# clock_prototype.net
KiCad netlist of a schematic drawn in EAGLE
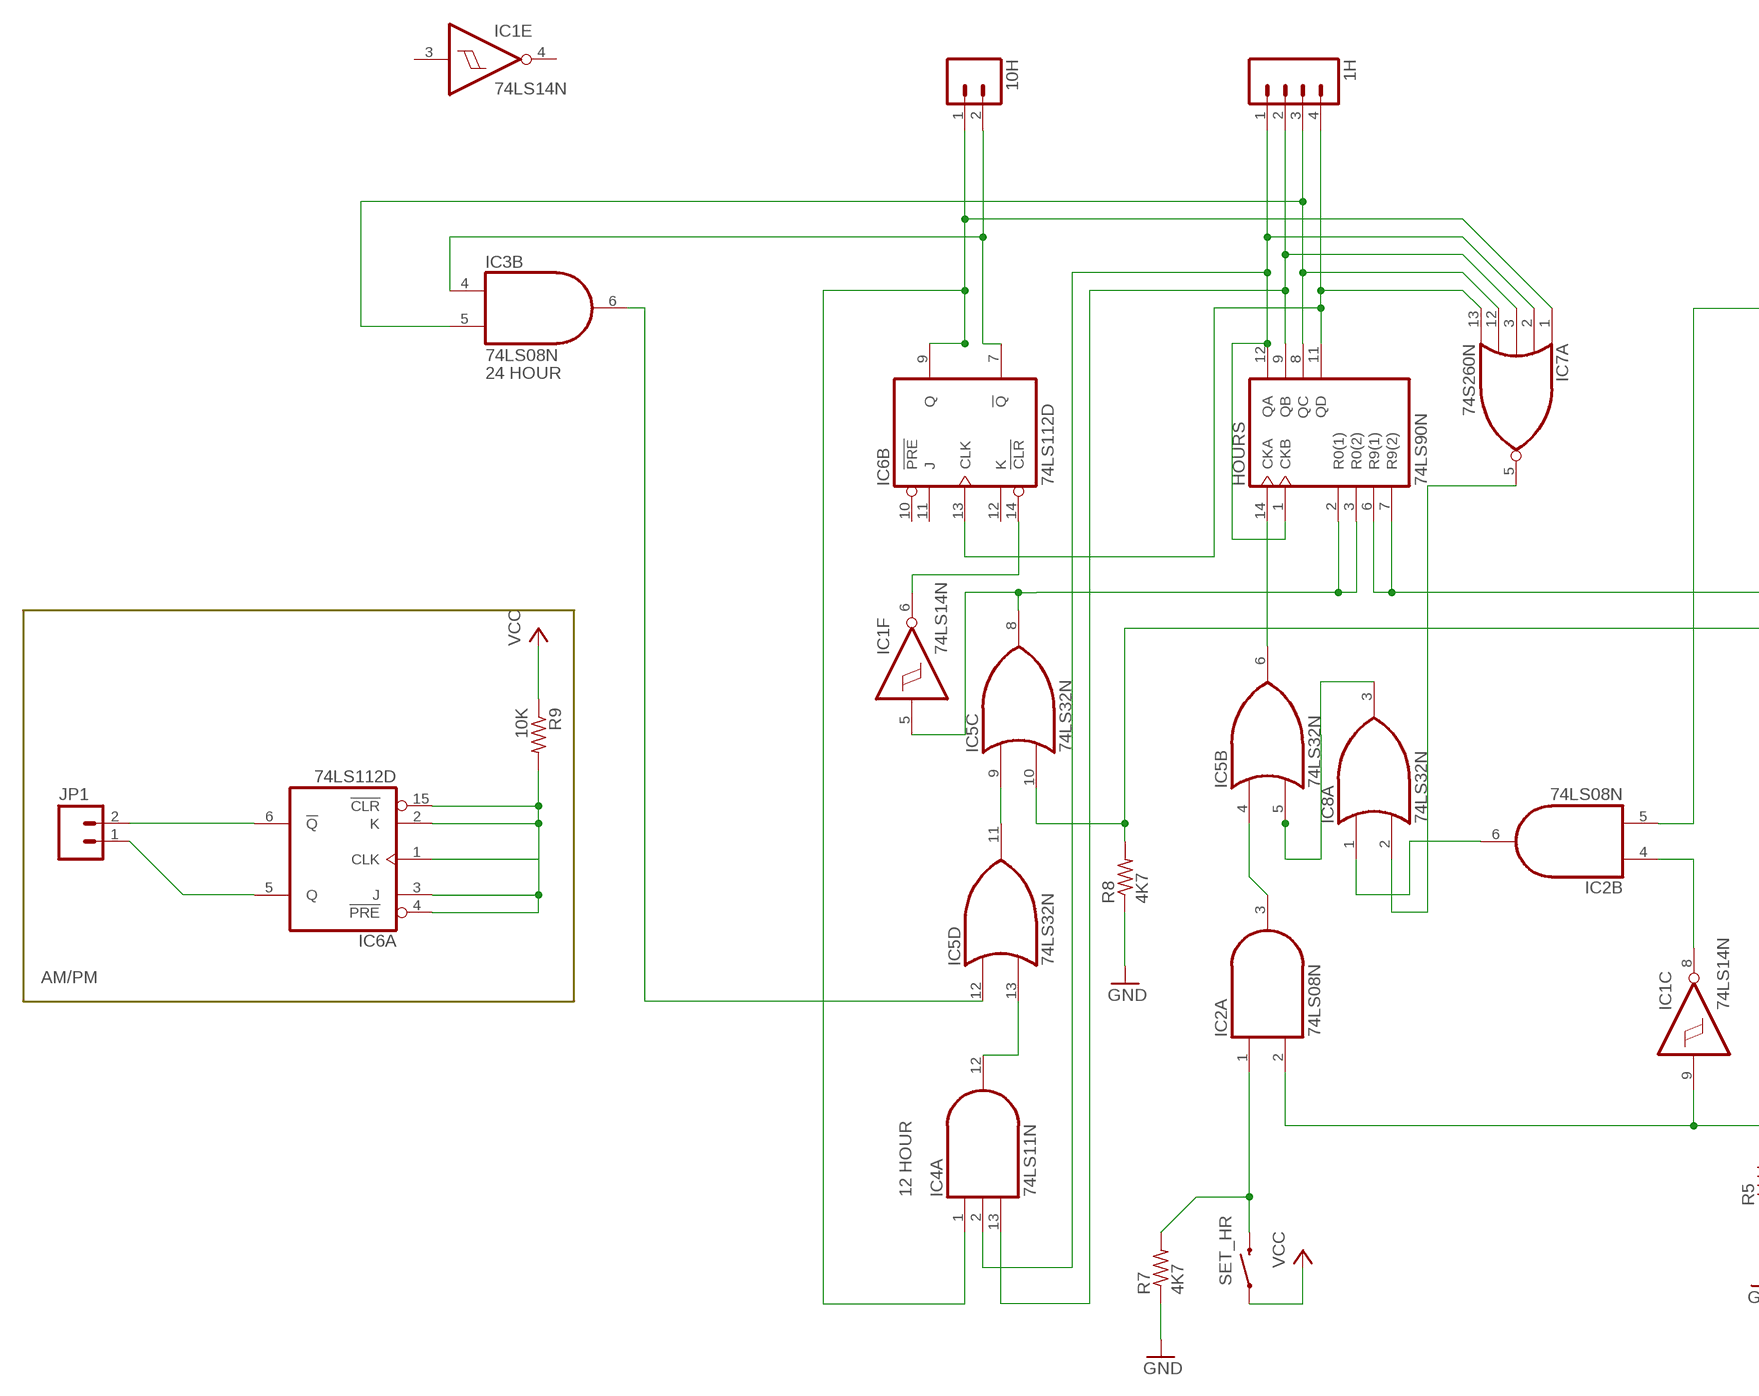
[diagram p0: schematic, sheet 1, part 1 of 2]
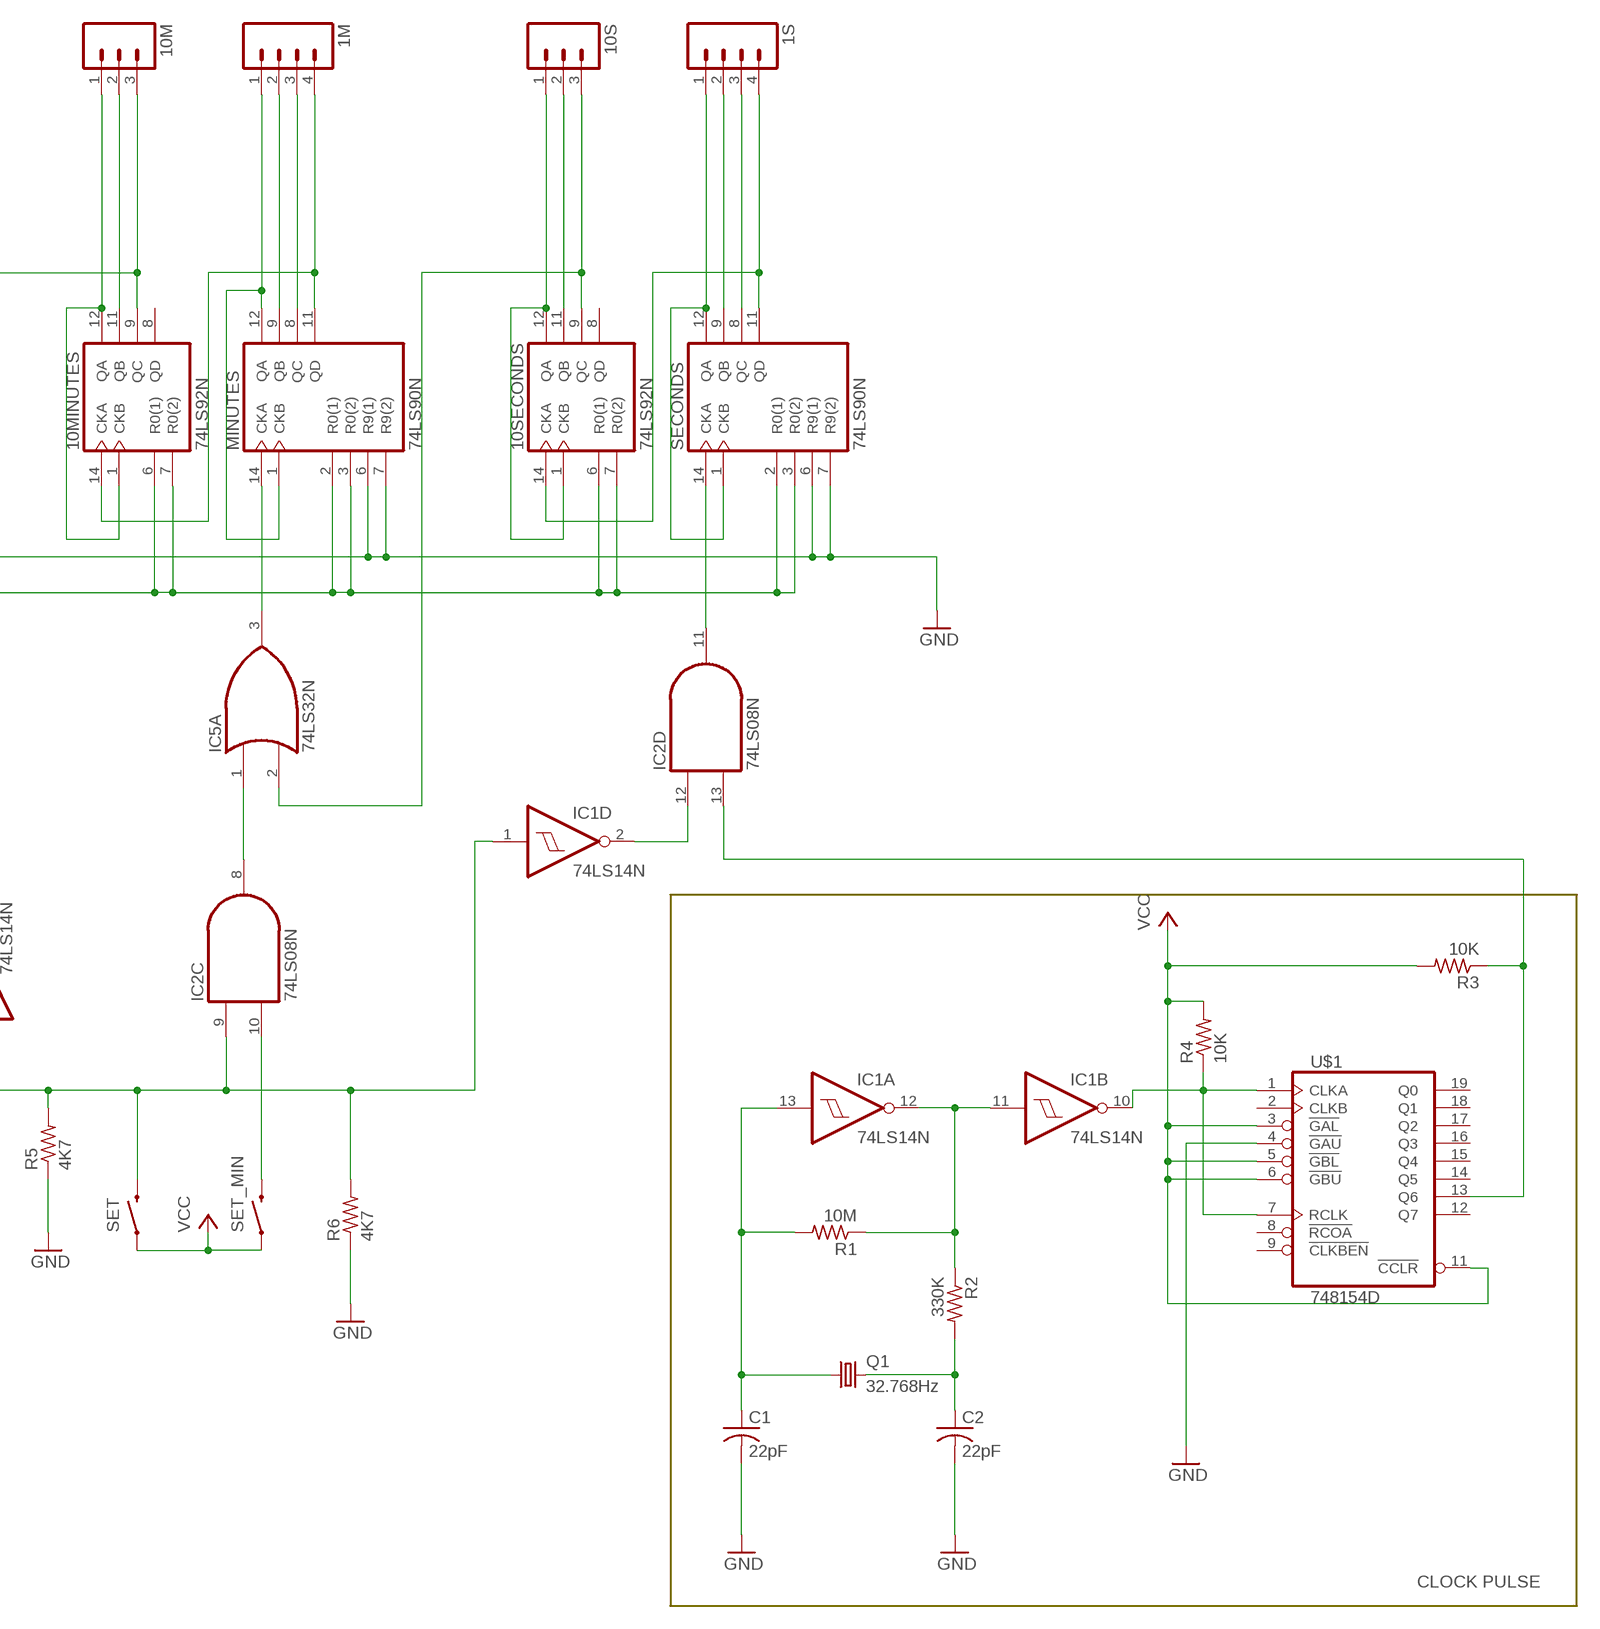
[diagram p1: schematic, sheet 1, part 2 of 2]

(export (version "E")
  (design (tool "Eeschema 10.0.6"))
  (components
    (comp (ref "1H")
      (value "M04PTH")
      (footprint "eagle-import:1X04")
      (libsource (lib "eagle-import") (part "M04PTH"))
    )
    (comp (ref "1M")
      (value "M04PTH")
      (footprint "eagle-import:1X04")
      (libsource (lib "eagle-import") (part "M04PTH"))
    )
    (comp (ref "1S")
      (value "M04PTH")
      (footprint "eagle-import:1X04")
      (libsource (lib "eagle-import") (part "M04PTH"))
    )
    (comp (ref "10H")
      (value "M02PTH")
      (footprint "eagle-import:1X02")
      (libsource (lib "eagle-import") (part "M02PTH"))
    )
    (comp (ref "10M")
      (value "M03PTH")
      (footprint "eagle-import:1X03")
      (libsource (lib "eagle-import") (part "M03PTH"))
    )
    (comp (ref "10MINUTES")
      (value "74LS92N")
      (footprint "eagle-import:DIL14")
      (libsource (lib "eagle-import") (part "7492NLS"))
    )
    (comp (ref "10S")
      (value "M03PTH")
      (footprint "eagle-import:1X03")
      (libsource (lib "eagle-import") (part "M03PTH"))
    )
    (comp (ref "10SECONDS")
      (value "74LS92N")
      (footprint "eagle-import:DIL14")
      (libsource (lib "eagle-import") (part "7492NLS"))
    )
    (comp (ref "C1")
      (value "22pF")
      (footprint "eagle-import:C050-024X044")
      (libsource (lib "eagle-import") (part "CAPACITOR050-024X044"))
    )
    (comp (ref "C2")
      (value "22pF")
      (footprint "eagle-import:C050-024X044")
      (libsource (lib "eagle-import") (part "CAPACITOR050-024X044"))
    )
    (comp (ref "HOURS")
      (value "74LS90N")
      (footprint "eagle-import:DIL14")
      (libsource (lib "eagle-import") (part "7490NLS"))
    )
    (comp (ref "IC1")
      (value "74LS14N")
      (footprint "eagle-import:DIL14")
      (libsource (lib "eagle-import") (part "7414NLS"))
    )
    (comp (ref "IC2")
      (value "74LS08N")
      (footprint "eagle-import:DIL14")
      (libsource (lib "eagle-import") (part "7408NLS"))
    )
    (comp (ref "IC3")
      (value "74LS08N")
      (footprint "eagle-import:DIL14")
      (libsource (lib "eagle-import") (part "7408NLS"))
    )
    (comp (ref "IC4")
      (value "74LS11N")
      (footprint "eagle-import:DIL14")
      (libsource (lib "eagle-import") (part "7411NLS"))
    )
    (comp (ref "IC5")
      (value "74LS32N")
      (footprint "eagle-import:DIL14")
      (libsource (lib "eagle-import") (part "7432NLS"))
    )
    (comp (ref "IC6")
      (value "74LS112D")
      (footprint "eagle-import:SO16")
      (libsource (lib "eagle-import") (part "74112DLS"))
    )
    (comp (ref "IC7")
      (value "74S260N")
      (footprint "eagle-import:DIL14")
      (libsource (lib "eagle-import") (part "74260NS"))
    )
    (comp (ref "IC8")
      (value "74LS32N")
      (footprint "eagle-import:DIL14")
      (libsource (lib "eagle-import") (part "7432NLS"))
    )
    (comp (ref "JP1")
      (value "M02PTH")
      (footprint "eagle-import:1X02")
      (libsource (lib "eagle-import") (part "M02PTH"))
    )
    (comp (ref "MINUTES")
      (value "74LS90N")
      (footprint "eagle-import:DIL14")
      (libsource (lib "eagle-import") (part "7490NLS"))
    )
    (comp (ref "Q1")
      (value "32.768Hz")
      (footprint "eagle-import:TC26V")
      (libsource (lib "eagle-import") (part "CRYSTALTC26V"))
    )
    (comp (ref "R1")
      (value "10M")
      (footprint "eagle-import:0207_7")
      (libsource (lib "eagle-import") (part "RESISTOR0207/7"))
    )
    (comp (ref "R2")
      (value "330K")
      (footprint "eagle-import:0207_7")
      (libsource (lib "eagle-import") (part "RESISTOR0207/7"))
    )
    (comp (ref "R3")
      (value "10K")
      (footprint "eagle-import:0207_7")
      (libsource (lib "eagle-import") (part "RESISTOR0207/7"))
    )
    (comp (ref "R4")
      (value "10K")
      (footprint "eagle-import:0207_7")
      (libsource (lib "eagle-import") (part "RESISTOR0207/7"))
    )
    (comp (ref "R5")
      (value "4K7")
      (footprint "eagle-import:0207_7")
      (libsource (lib "eagle-import") (part "RESISTOR0207/7"))
    )
    (comp (ref "R6")
      (value "4K7")
      (footprint "eagle-import:0207_7")
      (libsource (lib "eagle-import") (part "RESISTOR0207/7"))
    )
    (comp (ref "R7")
      (value "4K7")
      (footprint "eagle-import:0207_7")
      (libsource (lib "eagle-import") (part "RESISTOR0207/7"))
    )
    (comp (ref "R8")
      (value "4K7")
      (footprint "eagle-import:0207_7")
      (libsource (lib "eagle-import") (part "RESISTOR0207/7"))
    )
    (comp (ref "R9")
      (value "10K")
      (footprint "eagle-import:0207_7")
      (libsource (lib "eagle-import") (part "RESISTOR0207/7"))
    )
    (comp (ref "SECONDS")
      (value "74LS90N")
      (footprint "eagle-import:DIL14")
      (libsource (lib "eagle-import") (part "7490NLS"))
    )
    (comp (ref "SET")
      (value "SWITCH-MOMENTARY12MM")
      (footprint "eagle-import:TACTILE-PTH-12MM")
      (libsource (lib "eagle-import") (part "SWITCH-MOMENTARY12MM"))
    )
    (comp (ref "SET_HR")
      (value "SWITCH-MOMENTARY12MM")
      (footprint "eagle-import:TACTILE-PTH-12MM")
      (libsource (lib "eagle-import") (part "SWITCH-MOMENTARY12MM"))
    )
    (comp (ref "SET_MIN")
      (value "SWITCH-MOMENTARY12MM")
      (footprint "eagle-import:TACTILE-PTH-12MM")
      (libsource (lib "eagle-import") (part "SWITCH-MOMENTARY12MM"))
    )
    (comp (ref "U$1")
      (value "748154D")
      (footprint "eagle-import:TSSOP20")
      (libsource (lib "eagle-import") (part "748154D"))
    )
  )
  (nets
    (net (code "1") (name "GND") (class "Default")
      (node (ref "C1") (pin "2") (pinfunction "2_2") (pintype "passive"))
      (node (ref "C2") (pin "2") (pinfunction "2_2") (pintype "passive"))
      (node (ref "HOURS") (pin "6") (pinfunction "R9(1)_6") (pintype "input"))
      (node (ref "HOURS") (pin "7") (pinfunction "R9(2)_7") (pintype "input"))
      (node (ref "MINUTES") (pin "6") (pinfunction "R9(1)_6") (pintype "input"))
      (node (ref "MINUTES") (pin "7") (pinfunction "R9(2)_7") (pintype "input"))
      (node (ref "R5") (pin "1") (pinfunction "1_1") (pintype "passive"))
      (node (ref "R6") (pin "1") (pinfunction "1_1") (pintype "passive"))
      (node (ref "R7") (pin "1") (pinfunction "1_1") (pintype "passive"))
      (node (ref "R8") (pin "1") (pinfunction "1_1") (pintype "passive"))
      (node (ref "SECONDS") (pin "6") (pinfunction "R9(1)_6") (pintype "input"))
      (node (ref "SECONDS") (pin "7") (pinfunction "R9(2)_7") (pintype "input"))
      (node (ref "U$1") (pin "4") (pinfunction "~{GAU}_4") (pintype "input"))
    )
    (net (code "2") (name "Net-(10MINUTESA-CKA)") (class "Default")
      (node (ref "10MINUTES") (pin "14") (pinfunction "CKA_14") (pintype "input"))
      (node (ref "1M") (pin "4") (pinfunction "4_4") (pintype "passive"))
      (node (ref "MINUTES") (pin "11") (pinfunction "QD_11") (pintype "output"))
    )
    (net (code "3") (name "Net-(10MINUTESA-CKB)") (class "Default")
      (node (ref "10M") (pin "1") (pinfunction "1_1") (pintype "passive"))
      (node (ref "10MINUTES") (pin "1") (pinfunction "CKB_1") (pintype "input"))
      (node (ref "10MINUTES") (pin "12") (pinfunction "QA_12") (pintype "output"))
    )
    (net (code "4") (name "Net-(10MINUTESA-QB)") (class "Default")
      (node (ref "10M") (pin "2") (pinfunction "2_2") (pintype "passive"))
      (node (ref "10MINUTES") (pin "11") (pinfunction "QB_11") (pintype "output"))
    )
    (net (code "5") (name "Net-(10MINUTESA-QC)") (class "Default")
      (node (ref "10M") (pin "3") (pinfunction "3_3") (pintype "passive"))
      (node (ref "10MINUTES") (pin "9") (pinfunction "QC_9") (pintype "output"))
      (node (ref "IC2") (pin "5") (pinfunction "I1_5") (pintype "input"))
    )
    (net (code "6") (name "Net-(10MINUTESA-R0(1))") (class "Default")
      (node (ref "10MINUTES") (pin "6") (pinfunction "R0(1)_6") (pintype "input"))
      (node (ref "10MINUTES") (pin "7") (pinfunction "R0(2)_7") (pintype "input"))
      (node (ref "10SECONDS") (pin "6") (pinfunction "R0(1)_6") (pintype "input"))
      (node (ref "10SECONDS") (pin "7") (pinfunction "R0(2)_7") (pintype "input"))
      (node (ref "IC5") (pin "10") (pinfunction "I1_10") (pintype "input"))
      (node (ref "MINUTES") (pin "2") (pinfunction "R0(1)_2") (pintype "input"))
      (node (ref "MINUTES") (pin "3") (pinfunction "R0(2)_3") (pintype "input"))
      (node (ref "R8") (pin "2") (pinfunction "2_2") (pintype "passive"))
      (node (ref "SECONDS") (pin "2") (pinfunction "R0(1)_2") (pintype "input"))
      (node (ref "SECONDS") (pin "3") (pinfunction "R0(2)_3") (pintype "input"))
    )
    (net (code "7") (name "Net-(10SECONDSA-CKA)") (class "Default")
      (node (ref "10SECONDS") (pin "14") (pinfunction "CKA_14") (pintype "input"))
      (node (ref "1S") (pin "4") (pinfunction "4_4") (pintype "passive"))
      (node (ref "SECONDS") (pin "11") (pinfunction "QD_11") (pintype "output"))
    )
    (net (code "8") (name "Net-(10SECONDSA-CKB)") (class "Default")
      (node (ref "10S") (pin "1") (pinfunction "1_1") (pintype "passive"))
      (node (ref "10SECONDS") (pin "1") (pinfunction "CKB_1") (pintype "input"))
      (node (ref "10SECONDS") (pin "12") (pinfunction "QA_12") (pintype "output"))
    )
    (net (code "9") (name "Net-(10SECONDSA-QB)") (class "Default")
      (node (ref "10S") (pin "2") (pinfunction "2_2") (pintype "passive"))
      (node (ref "10SECONDS") (pin "11") (pinfunction "QB_11") (pintype "output"))
    )
    (net (code "10") (name "Net-(10SECONDSA-QC)") (class "Default")
      (node (ref "10S") (pin "3") (pinfunction "3_3") (pintype "passive"))
      (node (ref "10SECONDS") (pin "9") (pinfunction "QC_9") (pintype "output"))
      (node (ref "IC5") (pin "2") (pinfunction "I1_2") (pintype "input"))
    )
    (net (code "11") (name "Net-(C2-Pad1)") (class "Default")
      (node (ref "C2") (pin "1") (pinfunction "1_1") (pintype "passive"))
      (node (ref "Q1") (pin "2") (pinfunction "2_2") (pintype "passive"))
      (node (ref "R2") (pin "2") (pinfunction "2_2") (pintype "passive"))
    )
    (net (code "12") (name "Net-(HOURSA-CKA)") (class "Default")
      (node (ref "HOURS") (pin "14") (pinfunction "CKA_14") (pintype "input"))
      (node (ref "IC5") (pin "6") (pinfunction "O_6") (pintype "output"))
    )
    (net (code "13") (name "Net-(HOURSA-CKB)") (class "Default")
      (node (ref "1H") (pin "1") (pinfunction "1_1") (pintype "passive"))
      (node (ref "HOURS") (pin "1") (pinfunction "CKB_1") (pintype "input"))
      (node (ref "HOURS") (pin "12") (pinfunction "QA_12") (pintype "output"))
      (node (ref "IC4") (pin "2") (pinfunction "I1_2") (pintype "input"))
      (node (ref "IC7") (pin "2") (pinfunction "I1_2") (pintype "input"))
    )
    (net (code "14") (name "Net-(HOURSA-QB)") (class "Default")
      (node (ref "1H") (pin "2") (pinfunction "2_2") (pintype "passive"))
      (node (ref "HOURS") (pin "9") (pinfunction "QB_9") (pintype "output"))
      (node (ref "IC4") (pin "13") (pinfunction "I2_13") (pintype "input"))
      (node (ref "IC7") (pin "3") (pinfunction "I2_3") (pintype "input"))
    )
    (net (code "15") (name "Net-(HOURSA-QC)") (class "Default")
      (node (ref "1H") (pin "3") (pinfunction "3_3") (pintype "passive"))
      (node (ref "HOURS") (pin "8") (pinfunction "QC_8") (pintype "output"))
      (node (ref "IC3") (pin "5") (pinfunction "I1_5") (pintype "input"))
      (node (ref "IC7") (pin "12") (pinfunction "I3_12") (pintype "input"))
    )
    (net (code "16") (name "Net-(HOURSA-QD)") (class "Default")
      (node (ref "1H") (pin "4") (pinfunction "4_4") (pintype "passive"))
      (node (ref "HOURS") (pin "11") (pinfunction "QD_11") (pintype "output"))
      (node (ref "IC6") (pin "13") (pinfunction "CLK_13") (pintype "input"))
      (node (ref "IC7") (pin "13") (pinfunction "I4_13") (pintype "input"))
    )
    (net (code "17") (name "Net-(HOURSA-R0(1))") (class "Default")
      (node (ref "HOURS") (pin "2") (pinfunction "R0(1)_2") (pintype "input"))
      (node (ref "HOURS") (pin "3") (pinfunction "R0(2)_3") (pintype "input"))
      (node (ref "IC1") (pin "5") (pinfunction "I_5") (pintype "input"))
      (node (ref "IC5") (pin "8") (pinfunction "O_8") (pintype "output"))
    )
    (net (code "18") (name "Net-(IC1A-I)") (class "Default")
      (node (ref "C1") (pin "1") (pinfunction "1_1") (pintype "passive"))
      (node (ref "IC1") (pin "13") (pinfunction "I_13") (pintype "input"))
      (node (ref "Q1") (pin "1") (pinfunction "1_1") (pintype "passive"))
      (node (ref "R1") (pin "2") (pinfunction "2_2") (pintype "passive"))
    )
    (net (code "19") (name "Net-(IC1A-O)") (class "Default")
      (node (ref "IC1") (pin "11") (pinfunction "I_11") (pintype "input"))
      (node (ref "IC1") (pin "12") (pinfunction "O_12") (pintype "output"))
      (node (ref "R1") (pin "1") (pinfunction "1_1") (pintype "passive"))
      (node (ref "R2") (pin "1") (pinfunction "1_1") (pintype "passive"))
    )
    (net (code "20") (name "Net-(IC1B-O)") (class "Default")
      (node (ref "IC1") (pin "10") (pinfunction "O_10") (pintype "output"))
      (node (ref "R4") (pin "1") (pinfunction "1_1") (pintype "passive"))
      (node (ref "U$1") (pin "1") (pinfunction "CLKA_1") (pintype "input"))
      (node (ref "U$1") (pin "7") (pinfunction "RCLK_7") (pintype "input"))
    )
    (net (code "21") (name "Net-(IC1C-I)") (class "Default")
      (node (ref "IC1") (pin "1") (pinfunction "I_1") (pintype "input"))
      (node (ref "IC1") (pin "9") (pinfunction "I_9") (pintype "input"))
      (node (ref "IC2") (pin "2") (pinfunction "I1_2") (pintype "input"))
      (node (ref "IC2") (pin "9") (pinfunction "I0_9") (pintype "input"))
      (node (ref "R5") (pin "2") (pinfunction "2_2") (pintype "passive"))
      (node (ref "R6") (pin "2") (pinfunction "2_2") (pintype "passive"))
      (node (ref "SET") (pin "3") (pinfunction "2_3") (pintype "passive"))
      (node (ref "SET") (pin "4") (pinfunction "2_4") (pintype "passive"))
    )
    (net (code "22") (name "Net-(IC1C-O)") (class "Default")
      (node (ref "IC1") (pin "8") (pinfunction "O_8") (pintype "output"))
      (node (ref "IC2") (pin "4") (pinfunction "I0_4") (pintype "input"))
    )
    (net (code "23") (name "Net-(IC1D-O)") (class "Default")
      (node (ref "IC1") (pin "2") (pinfunction "O_2") (pintype "output"))
      (node (ref "IC2") (pin "12") (pinfunction "I0_12") (pintype "input"))
    )
    (net (code "24") (name "Net-(IC1F-O)") (class "Default")
      (node (ref "IC1") (pin "6") (pinfunction "O_6") (pintype "output"))
      (node (ref "IC6") (pin "14") (pinfunction "~{CLR}_14") (pintype "input"))
    )
    (net (code "25") (name "Net-(IC2A-I0)") (class "Default")
      (node (ref "IC2") (pin "1") (pinfunction "I0_1") (pintype "input"))
      (node (ref "R7") (pin "2") (pinfunction "2_2") (pintype "passive"))
      (node (ref "SET_HR") (pin "3") (pinfunction "2_3") (pintype "passive"))
      (node (ref "SET_HR") (pin "4") (pinfunction "2_4") (pintype "passive"))
    )
    (net (code "26") (name "Net-(IC2A-O)") (class "Default")
      (node (ref "IC2") (pin "3") (pinfunction "O_3") (pintype "output"))
      (node (ref "IC5") (pin "4") (pinfunction "I0_4") (pintype "input"))
    )
    (net (code "27") (name "Net-(IC2B-O)") (class "Default")
      (node (ref "IC2") (pin "6") (pinfunction "O_6") (pintype "output"))
      (node (ref "IC8") (pin "1") (pinfunction "I0_1") (pintype "input"))
    )
    (net (code "28") (name "Net-(IC2C-I1)") (class "Default")
      (node (ref "IC2") (pin "10") (pinfunction "I1_10") (pintype "input"))
      (node (ref "SET_MIN") (pin "3") (pinfunction "2_3") (pintype "passive"))
      (node (ref "SET_MIN") (pin "4") (pinfunction "2_4") (pintype "passive"))
    )
    (net (code "29") (name "Net-(IC2C-O)") (class "Default")
      (node (ref "IC2") (pin "8") (pinfunction "O_8") (pintype "output"))
      (node (ref "IC5") (pin "1") (pinfunction "I0_1") (pintype "input"))
    )
    (net (code "30") (name "Net-(IC2D-I1)") (class "Default")
      (node (ref "IC2") (pin "13") (pinfunction "I1_13") (pintype "input"))
      (node (ref "R3") (pin "1") (pinfunction "1_1") (pintype "passive"))
      (node (ref "U$1") (pin "13") (pinfunction "Q6_13") (pintype "tri_state"))
    )
    (net (code "31") (name "Net-(IC2D-O)") (class "Default")
      (node (ref "IC2") (pin "11") (pinfunction "O_11") (pintype "output"))
      (node (ref "SECONDS") (pin "14") (pinfunction "CKA_14") (pintype "input"))
    )
    (net (code "32") (name "Net-(IC3B-I0)") (class "Default")
      (node (ref "10H") (pin "2") (pinfunction "2_2") (pintype "passive"))
      (node (ref "IC3") (pin "4") (pinfunction "I0_4") (pintype "input"))
      (node (ref "IC6") (pin "7") (pinfunction "~{Q}_7") (pintype "output"))
    )
    (net (code "33") (name "Net-(IC3B-O)") (class "Default")
      (node (ref "IC3") (pin "6") (pinfunction "O_6") (pintype "output"))
      (node (ref "IC5") (pin "12") (pinfunction "I0_12") (pintype "input"))
    )
    (net (code "34") (name "Net-(IC4A-I0)") (class "Default")
      (node (ref "10H") (pin "1") (pinfunction "1_1") (pintype "passive"))
      (node (ref "IC4") (pin "1") (pinfunction "I0_1") (pintype "input"))
      (node (ref "IC6") (pin "9") (pinfunction "Q_9") (pintype "output"))
      (node (ref "IC7") (pin "1") (pinfunction "I0_1") (pintype "input"))
    )
    (net (code "35") (name "Net-(IC4A-O)") (class "Default")
      (node (ref "IC4") (pin "12") (pinfunction "O_12") (pintype "output"))
      (node (ref "IC5") (pin "13") (pinfunction "I1_13") (pintype "input"))
    )
    (net (code "36") (name "Net-(IC5A-O)") (class "Default")
      (node (ref "IC5") (pin "3") (pinfunction "O_3") (pintype "output"))
      (node (ref "MINUTES") (pin "14") (pinfunction "CKA_14") (pintype "input"))
    )
    (net (code "37") (name "Net-(IC5B-I1)") (class "Default")
      (node (ref "IC5") (pin "5") (pinfunction "I1_5") (pintype "input"))
      (node (ref "IC8") (pin "3") (pinfunction "O_3") (pintype "output"))
    )
    (net (code "38") (name "Net-(IC5C-I0)") (class "Default")
      (node (ref "IC5") (pin "11") (pinfunction "O_11") (pintype "output"))
      (node (ref "IC5") (pin "9") (pinfunction "I0_9") (pintype "input"))
    )
    (net (code "39") (name "Net-(IC6A-J)") (class "Default")
      (node (ref "IC6") (pin "15") (pinfunction "~{CLR}_15") (pintype "input"))
      (node (ref "IC6") (pin "2") (pinfunction "K_2") (pintype "input"))
      (node (ref "IC6") (pin "3") (pinfunction "J_3") (pintype "input"))
      (node (ref "IC6") (pin "4") (pinfunction "~{PRE}_4") (pintype "input"))
      (node (ref "R9") (pin "2") (pinfunction "2_2") (pintype "passive"))
    )
    (net (code "40") (name "Net-(IC6A-Q)") (class "Default")
      (node (ref "IC6") (pin "5") (pinfunction "Q_5") (pintype "output"))
      (node (ref "JP1") (pin "1") (pinfunction "1_1") (pintype "passive"))
    )
    (net (code "41") (name "Net-(IC6A-~{Q})") (class "Default")
      (node (ref "IC6") (pin "6") (pinfunction "~{Q}_6") (pintype "output"))
      (node (ref "JP1") (pin "2") (pinfunction "2_2") (pintype "passive"))
    )
    (net (code "42") (name "Net-(IC7A-O)") (class "Default")
      (node (ref "IC7") (pin "5") (pinfunction "O_5") (pintype "output"))
      (node (ref "IC8") (pin "2") (pinfunction "I1_2") (pintype "input"))
    )
    (net (code "43") (name "Net-(MINUTESA-CKB)") (class "Default")
      (node (ref "1M") (pin "1") (pinfunction "1_1") (pintype "passive"))
      (node (ref "MINUTES") (pin "1") (pinfunction "CKB_1") (pintype "input"))
      (node (ref "MINUTES") (pin "12") (pinfunction "QA_12") (pintype "output"))
    )
    (net (code "44") (name "Net-(MINUTESA-QB)") (class "Default")
      (node (ref "1M") (pin "2") (pinfunction "2_2") (pintype "passive"))
      (node (ref "MINUTES") (pin "9") (pinfunction "QB_9") (pintype "output"))
    )
    (net (code "45") (name "Net-(MINUTESA-QC)") (class "Default")
      (node (ref "1M") (pin "3") (pinfunction "3_3") (pintype "passive"))
      (node (ref "MINUTES") (pin "8") (pinfunction "QC_8") (pintype "output"))
    )
    (net (code "46") (name "Net-(SECONDSA-CKB)") (class "Default")
      (node (ref "1S") (pin "1") (pinfunction "1_1") (pintype "passive"))
      (node (ref "SECONDS") (pin "1") (pinfunction "CKB_1") (pintype "input"))
      (node (ref "SECONDS") (pin "12") (pinfunction "QA_12") (pintype "output"))
    )
    (net (code "47") (name "Net-(SECONDSA-QB)") (class "Default")
      (node (ref "1S") (pin "2") (pinfunction "2_2") (pintype "passive"))
      (node (ref "SECONDS") (pin "9") (pinfunction "QB_9") (pintype "output"))
    )
    (net (code "48") (name "Net-(SECONDSA-QC)") (class "Default")
      (node (ref "1S") (pin "3") (pinfunction "3_3") (pintype "passive"))
      (node (ref "SECONDS") (pin "8") (pinfunction "QC_8") (pintype "output"))
    )
    (net (code "49") (name "VCC") (class "Default")
      (node (ref "R3") (pin "2") (pinfunction "2_2") (pintype "passive"))
      (node (ref "R4") (pin "2") (pinfunction "2_2") (pintype "passive"))
      (node (ref "R9") (pin "1") (pinfunction "1_1") (pintype "passive"))
      (node (ref "SET") (pin "1") (pinfunction "1_1") (pintype "passive"))
      (node (ref "SET") (pin "2") (pinfunction "1_2") (pintype "passive"))
      (node (ref "SET_HR") (pin "1") (pinfunction "1_1") (pintype "passive"))
      (node (ref "SET_HR") (pin "2") (pinfunction "1_2") (pintype "passive"))
      (node (ref "SET_MIN") (pin "1") (pinfunction "1_1") (pintype "passive"))
      (node (ref "SET_MIN") (pin "2") (pinfunction "1_2") (pintype "passive"))
      (node (ref "U$1") (pin "11") (pinfunction "~{CCLR}_11") (pintype "output"))
      (node (ref "U$1") (pin "3") (pinfunction "~{GAL}_3") (pintype "input"))
      (node (ref "U$1") (pin "5") (pinfunction "~{GBL}_5") (pintype "input"))
      (node (ref "U$1") (pin "6") (pinfunction "~{GBU}_6") (pintype "input"))
    )
    (net (code "50") (name "unconnected-(10MINUTESA-QD-Pad8)") (class "Default")
      (node (ref "10MINUTES") (pin "8") (pinfunction "QD_8") (pintype "output"))
    )
    (net (code "51") (name "unconnected-(10SECONDSA-QD-Pad8)") (class "Default")
      (node (ref "10SECONDS") (pin "8") (pinfunction "QD_8") (pintype "output"))
    )
    (net (code "52") (name "unconnected-(IC1E-I-Pad3)") (class "Default")
      (node (ref "IC1") (pin "3") (pinfunction "I_3") (pintype "input"))
    )
    (net (code "53") (name "unconnected-(IC1E-O-Pad4)") (class "Default")
      (node (ref "IC1") (pin "4") (pinfunction "O_4") (pintype "output"))
    )
    (net (code "54") (name "unconnected-(IC6A-CLK-Pad1)") (class "Default")
      (node (ref "IC6") (pin "1") (pinfunction "CLK_1") (pintype "input"))
    )
    (net (code "55") (name "unconnected-(IC6B-J-Pad11)") (class "Default")
      (node (ref "IC6") (pin "11") (pinfunction "J_11") (pintype "input"))
    )
    (net (code "56") (name "unconnected-(IC6B-K-Pad12)") (class "Default")
      (node (ref "IC6") (pin "12") (pinfunction "K_12") (pintype "input"))
    )
    (net (code "57") (name "unconnected-(IC6B-~{PRE}-Pad10)") (class "Default")
      (node (ref "IC6") (pin "10") (pinfunction "~{PRE}_10") (pintype "input"))
    )
    (net (code "58") (name "unconnected-(U$1A-CLKB-Pad2)") (class "Default")
      (node (ref "U$1") (pin "2") (pinfunction "CLKB_2") (pintype "input"))
    )
    (net (code "59") (name "unconnected-(U$1A-Q0-Pad19)") (class "Default")
      (node (ref "U$1") (pin "19") (pinfunction "Q0_19") (pintype "tri_state"))
    )
    (net (code "60") (name "unconnected-(U$1A-Q1-Pad18)") (class "Default")
      (node (ref "U$1") (pin "18") (pinfunction "Q1_18") (pintype "tri_state"))
    )
    (net (code "61") (name "unconnected-(U$1A-Q2-Pad17)") (class "Default")
      (node (ref "U$1") (pin "17") (pinfunction "Q2_17") (pintype "tri_state"))
    )
    (net (code "62") (name "unconnected-(U$1A-Q3-Pad16)") (class "Default")
      (node (ref "U$1") (pin "16") (pinfunction "Q3_16") (pintype "tri_state"))
    )
    (net (code "63") (name "unconnected-(U$1A-Q4-Pad15)") (class "Default")
      (node (ref "U$1") (pin "15") (pinfunction "Q4_15") (pintype "tri_state"))
    )
    (net (code "64") (name "unconnected-(U$1A-Q5-Pad14)") (class "Default")
      (node (ref "U$1") (pin "14") (pinfunction "Q5_14") (pintype "tri_state"))
    )
    (net (code "65") (name "unconnected-(U$1A-Q7-Pad12)") (class "Default")
      (node (ref "U$1") (pin "12") (pinfunction "Q7_12") (pintype "tri_state"))
    )
    (net (code "66") (name "unconnected-(U$1A-~{CLKBEN}-Pad9)") (class "Default")
      (node (ref "U$1") (pin "9") (pinfunction "~{CLKBEN}_9") (pintype "input"))
    )
    (net (code "67") (name "unconnected-(U$1A-~{RCOA}-Pad8)") (class "Default")
      (node (ref "U$1") (pin "8") (pinfunction "~{RCOA}_8") (pintype "input"))
    )
  )
)
